# ftdifriend-usb.net
KiCad netlist of a schematic drawn in EAGLE
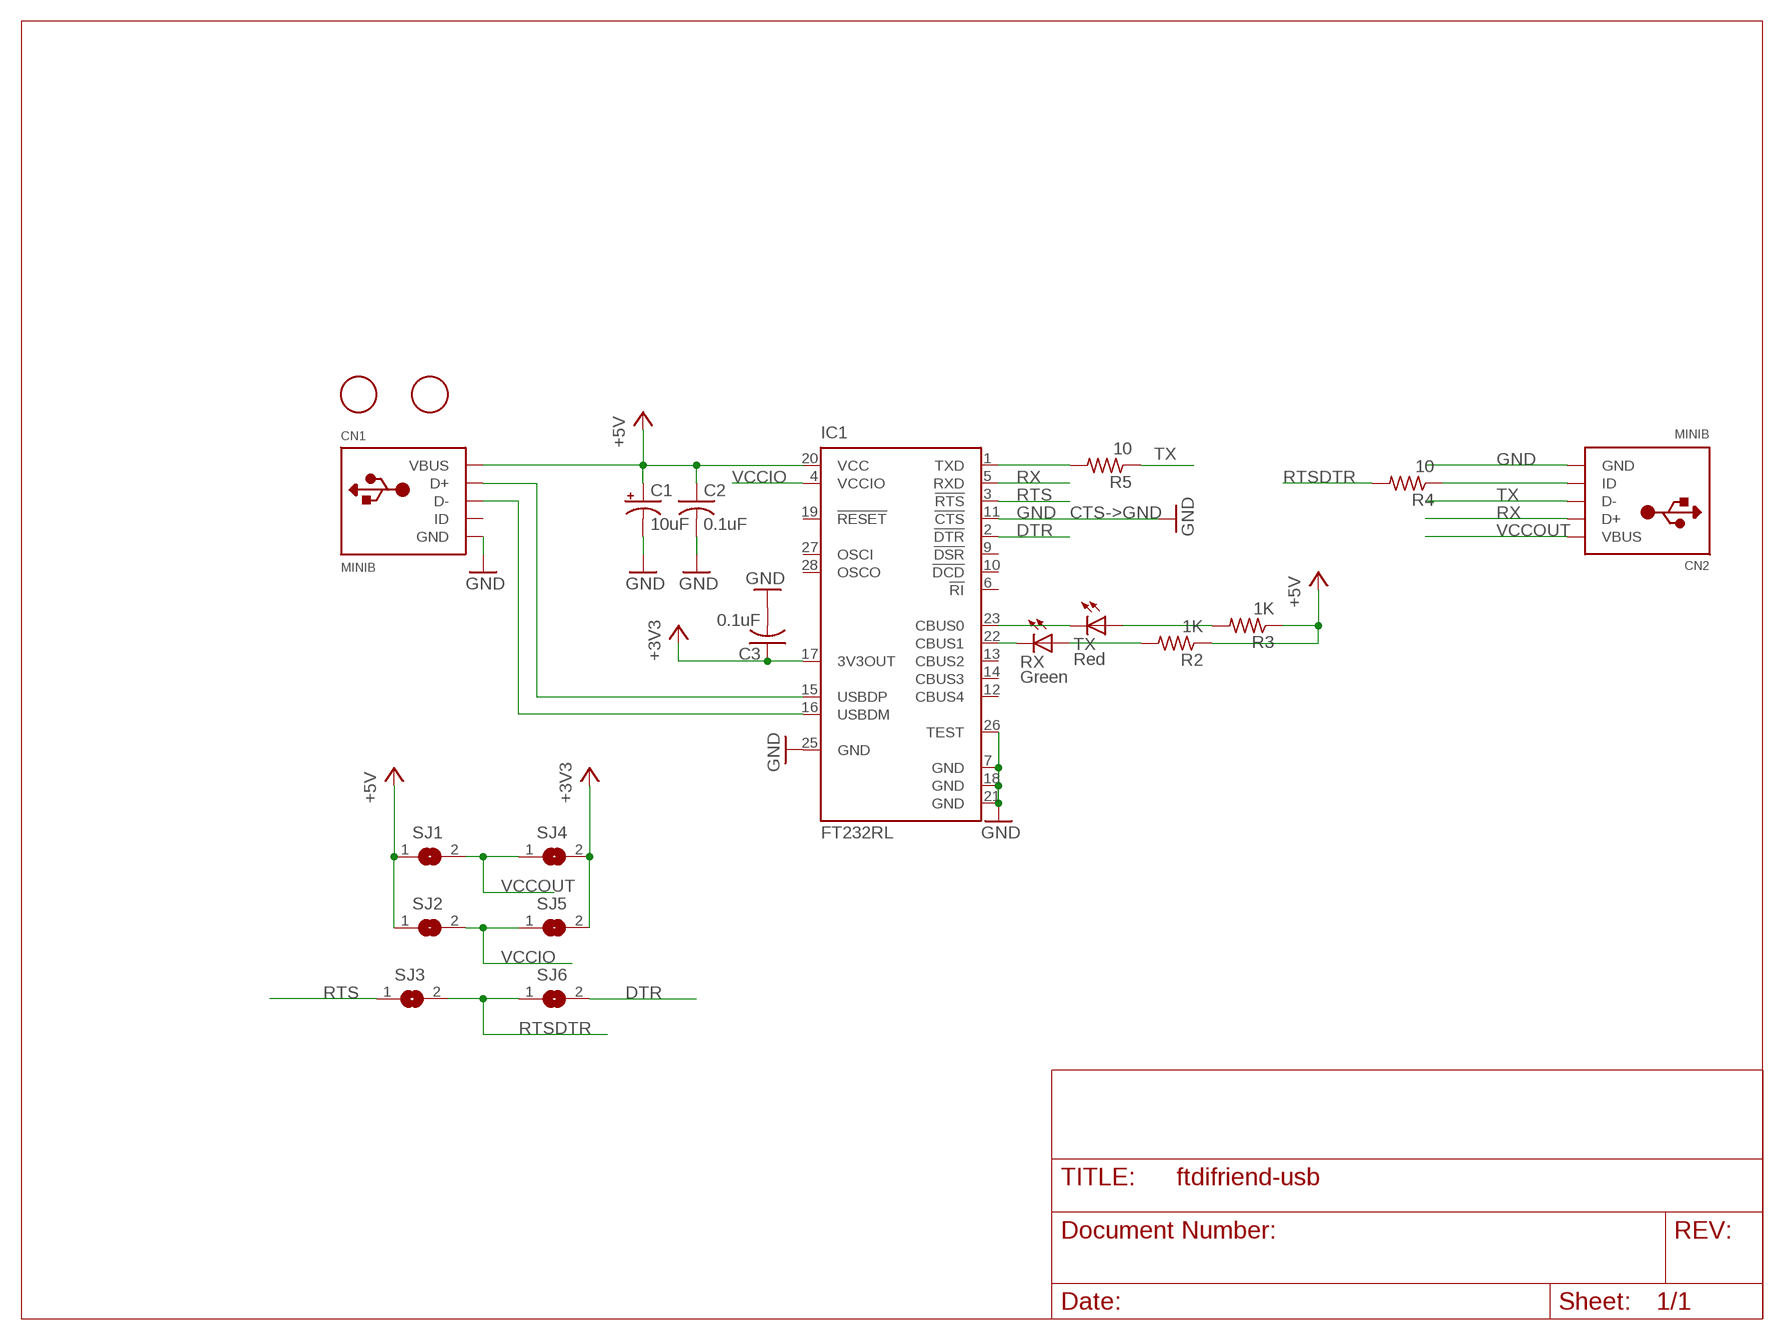
[diagram p0: schematic, sheet 1]

(export (version "E")
  (design (tool "Eeschema 10.0.6"))
  (components
    (comp (ref "C1")
      (value "10uF")
      (footprint "eagle-import:A_3216-18R")
      (libsource (lib "eagle-import") (part "CPOL-USA/3216-18R"))
    )
    (comp (ref "C2")
      (value "0.1uF")
      (footprint "eagle-import:C0805K")
      (libsource (lib "eagle-import") (part "C-USC0805K"))
    )
    (comp (ref "C3")
      (value "0.1uF")
      (footprint "eagle-import:C0805K")
      (libsource (lib "eagle-import") (part "C-USC0805K"))
    )
    (comp (ref "CN1")
      (value "MINIB")
      (footprint "eagle-import:USB-MINIB")
      (libsource (lib "eagle-import") (part "USBMINIB"))
    )
    (comp (ref "CN2")
      (value "MINIB")
      (footprint "eagle-import:USB-MINIB")
      (libsource (lib "eagle-import") (part "USBMINIB"))
    )
    (comp (ref "IC1")
      (value "FT232RL")
      (footprint "eagle-import:SSOP28")
      (libsource (lib "eagle-import") (part "FT232RL"))
    )
    (comp (ref "R2")
      (value "1K")
      (footprint "eagle-import:R0805")
      (libsource (lib "eagle-import") (part "R-US_R0805"))
    )
    (comp (ref "R3")
      (value "1K")
      (footprint "eagle-import:R0805")
      (libsource (lib "eagle-import") (part "R-US_R0805"))
    )
    (comp (ref "R4")
      (value "10")
      (footprint "eagle-import:R0805")
      (libsource (lib "eagle-import") (part "R-US_R0805"))
    )
    (comp (ref "R5")
      (value "10")
      (footprint "eagle-import:R0805")
      (libsource (lib "eagle-import") (part "R-US_R0805"))
    )
    (comp (ref "RX")
      (value "Green")
      (footprint "eagle-import:CHIP-LED0805")
      (libsource (lib "eagle-import") (part "LEDCHIP-LED0805"))
    )
    (comp (ref "SJ1") (value "SJ") (footprint "eagle-import:SJ") (libsource (lib "eagle-import") (part "SJ")))
    (comp (ref "SJ2") (value "SJ") (footprint "eagle-import:SJ") (libsource (lib "eagle-import") (part "SJ")))
    (comp (ref "SJ3") (value "SJ") (footprint "eagle-import:SJ") (libsource (lib "eagle-import") (part "SJ")))
    (comp (ref "SJ4") (value "SJ") (footprint "eagle-import:SJ") (libsource (lib "eagle-import") (part "SJ")))
    (comp (ref "SJ5") (value "SJ") (footprint "eagle-import:SJ") (libsource (lib "eagle-import") (part "SJ")))
    (comp (ref "SJ6") (value "SJ") (footprint "eagle-import:SJ") (libsource (lib "eagle-import") (part "SJ")))
    (comp (ref "TX")
      (value "Red")
      (footprint "eagle-import:CHIP-LED0805")
      (libsource (lib "eagle-import") (part "LEDCHIP-LED0805"))
    )
    (comp (ref "U$1")
      (value "FIDUCIAL")
      (footprint "eagle-import:FIDUCIAL_1MM")
      (libsource (lib "eagle-import") (part "FIDUCIAL"))
    )
    (comp (ref "U$2")
      (value "FIDUCIAL")
      (footprint "eagle-import:FIDUCIAL_1MM")
      (libsource (lib "eagle-import") (part "FIDUCIAL"))
    )
  )
  (nets
    (net (code "1") (name "+3V3") (class "Default")
      (node (ref "C3") (pin "1") (pinfunction "1_1") (pintype "passive"))
      (node (ref "IC1") (pin "17") (pinfunction "3V3OUT_17") (pintype "input"))
      (node (ref "SJ4") (pin "2") (pinfunction "2_2") (pintype "passive"))
      (node (ref "SJ5") (pin "2") (pinfunction "2_2") (pintype "passive"))
    )
    (net (code "2") (name "+5V") (class "Default")
      (node (ref "C1") (pin "+") (pinfunction "+_+") (pintype "passive"))
      (node (ref "C2") (pin "1") (pinfunction "1_1") (pintype "passive"))
      (node (ref "CN1") (pin "VBUS") (pinfunction "VBUS_VBUS") (pintype "power_in"))
      (node (ref "IC1") (pin "20") (pinfunction "VCC_20") (pintype "input"))
      (node (ref "R2") (pin "1") (pinfunction "1_1") (pintype "passive"))
      (node (ref "R3") (pin "1") (pinfunction "1_1") (pintype "passive"))
      (node (ref "SJ1") (pin "1") (pinfunction "1_1") (pintype "passive"))
      (node (ref "SJ2") (pin "1") (pinfunction "1_1") (pintype "passive"))
    )
    (net (code "3") (name "/DTR") (class "Default")
      (node (ref "IC1") (pin "2") (pinfunction "~{DTR}_2") (pintype "input"))
      (node (ref "SJ6") (pin "2") (pinfunction "2_2") (pintype "passive"))
    )
    (net (code "4") (name "/RTS") (class "Default")
      (node (ref "IC1") (pin "3") (pinfunction "~{RTS}_3") (pintype "input"))
      (node (ref "SJ3") (pin "1") (pinfunction "1_1") (pintype "passive"))
    )
    (net (code "5") (name "/RTSDTR") (class "Default")
      (node (ref "R4") (pin "2") (pinfunction "2_2") (pintype "passive"))
      (node (ref "SJ3") (pin "2") (pinfunction "2_2") (pintype "passive"))
      (node (ref "SJ6") (pin "1") (pinfunction "1_1") (pintype "passive"))
    )
    (net (code "6") (name "/RX") (class "Default")
      (node (ref "CN2") (pin "D+") (pinfunction "D+_D+") (pintype "bidirectional"))
      (node (ref "IC1") (pin "5") (pinfunction "RXD_5") (pintype "input"))
    )
    (net (code "7") (name "/TX") (class "Default")
      (node (ref "CN2") (pin "D-") (pinfunction "D-_D-") (pintype "bidirectional"))
      (node (ref "R5") (pin "1") (pinfunction "1_1") (pintype "passive"))
    )
    (net (code "8") (name "/VCCIO") (class "Default")
      (node (ref "IC1") (pin "4") (pinfunction "VCCIO_4") (pintype "input"))
      (node (ref "SJ2") (pin "2") (pinfunction "2_2") (pintype "passive"))
      (node (ref "SJ5") (pin "1") (pinfunction "1_1") (pintype "passive"))
    )
    (net (code "9") (name "/VCCOUT") (class "Default")
      (node (ref "CN2") (pin "VBUS") (pinfunction "VBUS_VBUS") (pintype "power_in"))
      (node (ref "SJ1") (pin "2") (pinfunction "2_2") (pintype "passive"))
      (node (ref "SJ4") (pin "1") (pinfunction "1_1") (pintype "passive"))
    )
    (net (code "10") (name "GND") (class "Default")
      (node (ref "C1") (pin "-") (pinfunction "-_-") (pintype "passive"))
      (node (ref "C2") (pin "2") (pinfunction "2_2") (pintype "passive"))
      (node (ref "C3") (pin "2") (pinfunction "2_2") (pintype "passive"))
      (node (ref "CN1") (pin "GND") (pinfunction "GND_GND") (pintype "power_in"))
      (node (ref "CN2") (pin "GND") (pinfunction "GND_GND") (pintype "power_in"))
      (node (ref "IC1") (pin "11") (pinfunction "~{CTS}_11") (pintype "input"))
      (node (ref "IC1") (pin "18") (pinfunction "GND_18") (pintype "input"))
      (node (ref "IC1") (pin "21") (pinfunction "GND_21") (pintype "input"))
      (node (ref "IC1") (pin "25") (pinfunction "GND_25") (pintype "input"))
      (node (ref "IC1") (pin "26") (pinfunction "TEST_26") (pintype "input"))
      (node (ref "IC1") (pin "7") (pinfunction "GND_7") (pintype "input"))
    )
    (net (code "11") (name "Net-(CN2-PadID)") (class "Default")
      (node (ref "CN2") (pin "ID") (pinfunction "ID_ID") (pintype "bidirectional"))
      (node (ref "R4") (pin "1") (pinfunction "1_1") (pintype "passive"))
    )
    (net (code "12") (name "Net-(IC1-CBUS0)") (class "Default")
      (node (ref "IC1") (pin "23") (pinfunction "CBUS0_23") (pintype "input"))
      (node (ref "TX") (pin "C") (pinfunction "C_C") (pintype "passive"))
    )
    (net (code "13") (name "Net-(IC1-CBUS1)") (class "Default")
      (node (ref "IC1") (pin "22") (pinfunction "CBUS1_22") (pintype "input"))
      (node (ref "RX") (pin "C") (pinfunction "C_C") (pintype "passive"))
    )
    (net (code "14") (name "Net-(IC1-TXD)") (class "Default")
      (node (ref "IC1") (pin "1") (pinfunction "TXD_1") (pintype "input"))
      (node (ref "R5") (pin "2") (pinfunction "2_2") (pintype "passive"))
    )
    (net (code "15") (name "Net-(IC1-USBDM)") (class "Default")
      (node (ref "CN1") (pin "D-") (pinfunction "D-_D-") (pintype "bidirectional"))
      (node (ref "IC1") (pin "16") (pinfunction "USBDM_16") (pintype "input"))
    )
    (net (code "16") (name "Net-(IC1-USBDP)") (class "Default")
      (node (ref "CN1") (pin "D+") (pinfunction "D+_D+") (pintype "bidirectional"))
      (node (ref "IC1") (pin "15") (pinfunction "USBDP_15") (pintype "input"))
    )
    (net (code "17") (name "Net-(R2-Pad2)") (class "Default")
      (node (ref "R2") (pin "2") (pinfunction "2_2") (pintype "passive"))
      (node (ref "RX") (pin "A") (pinfunction "A_A") (pintype "passive"))
    )
    (net (code "18") (name "Net-(R3-Pad2)") (class "Default")
      (node (ref "R3") (pin "2") (pinfunction "2_2") (pintype "passive"))
      (node (ref "TX") (pin "A") (pinfunction "A_A") (pintype "passive"))
    )
    (net (code "19") (name "unconnected-(CN1-PadID)") (class "Default")
      (node (ref "CN1") (pin "ID") (pinfunction "ID_ID") (pintype "bidirectional"))
    )
    (net (code "20") (name "unconnected-(IC1-CBUS2-Pad13)") (class "Default")
      (node (ref "IC1") (pin "13") (pinfunction "CBUS2_13") (pintype "input"))
    )
    (net (code "21") (name "unconnected-(IC1-CBUS3-Pad14)") (class "Default")
      (node (ref "IC1") (pin "14") (pinfunction "CBUS3_14") (pintype "input"))
    )
    (net (code "22") (name "unconnected-(IC1-CBUS4-Pad12)") (class "Default")
      (node (ref "IC1") (pin "12") (pinfunction "CBUS4_12") (pintype "input"))
    )
    (net (code "23") (name "unconnected-(IC1-OSCI-Pad27)") (class "Default")
      (node (ref "IC1") (pin "27") (pinfunction "OSCI_27") (pintype "input"))
    )
    (net (code "24") (name "unconnected-(IC1-OSCO-Pad28)") (class "Default")
      (node (ref "IC1") (pin "28") (pinfunction "OSCO_28") (pintype "input"))
    )
    (net (code "25") (name "unconnected-(IC1-~{DCD}-Pad10)") (class "Default")
      (node (ref "IC1") (pin "10") (pinfunction "~{DCD}_10") (pintype "input"))
    )
    (net (code "26") (name "unconnected-(IC1-~{DSR}-Pad9)") (class "Default")
      (node (ref "IC1") (pin "9") (pinfunction "~{DSR}_9") (pintype "input"))
    )
    (net (code "27") (name "unconnected-(IC1-~{RESET}-Pad19)") (class "Default")
      (node (ref "IC1") (pin "19") (pinfunction "~{RESET}_19") (pintype "input"))
    )
    (net (code "28") (name "unconnected-(IC1-~{RI}-Pad6)") (class "Default")
      (node (ref "IC1") (pin "6") (pinfunction "~{RI}_6") (pintype "input"))
    )
  )
)
